# POWER_SWITCH.net
KiCad netlist of a schematic drawn in Altium Designer
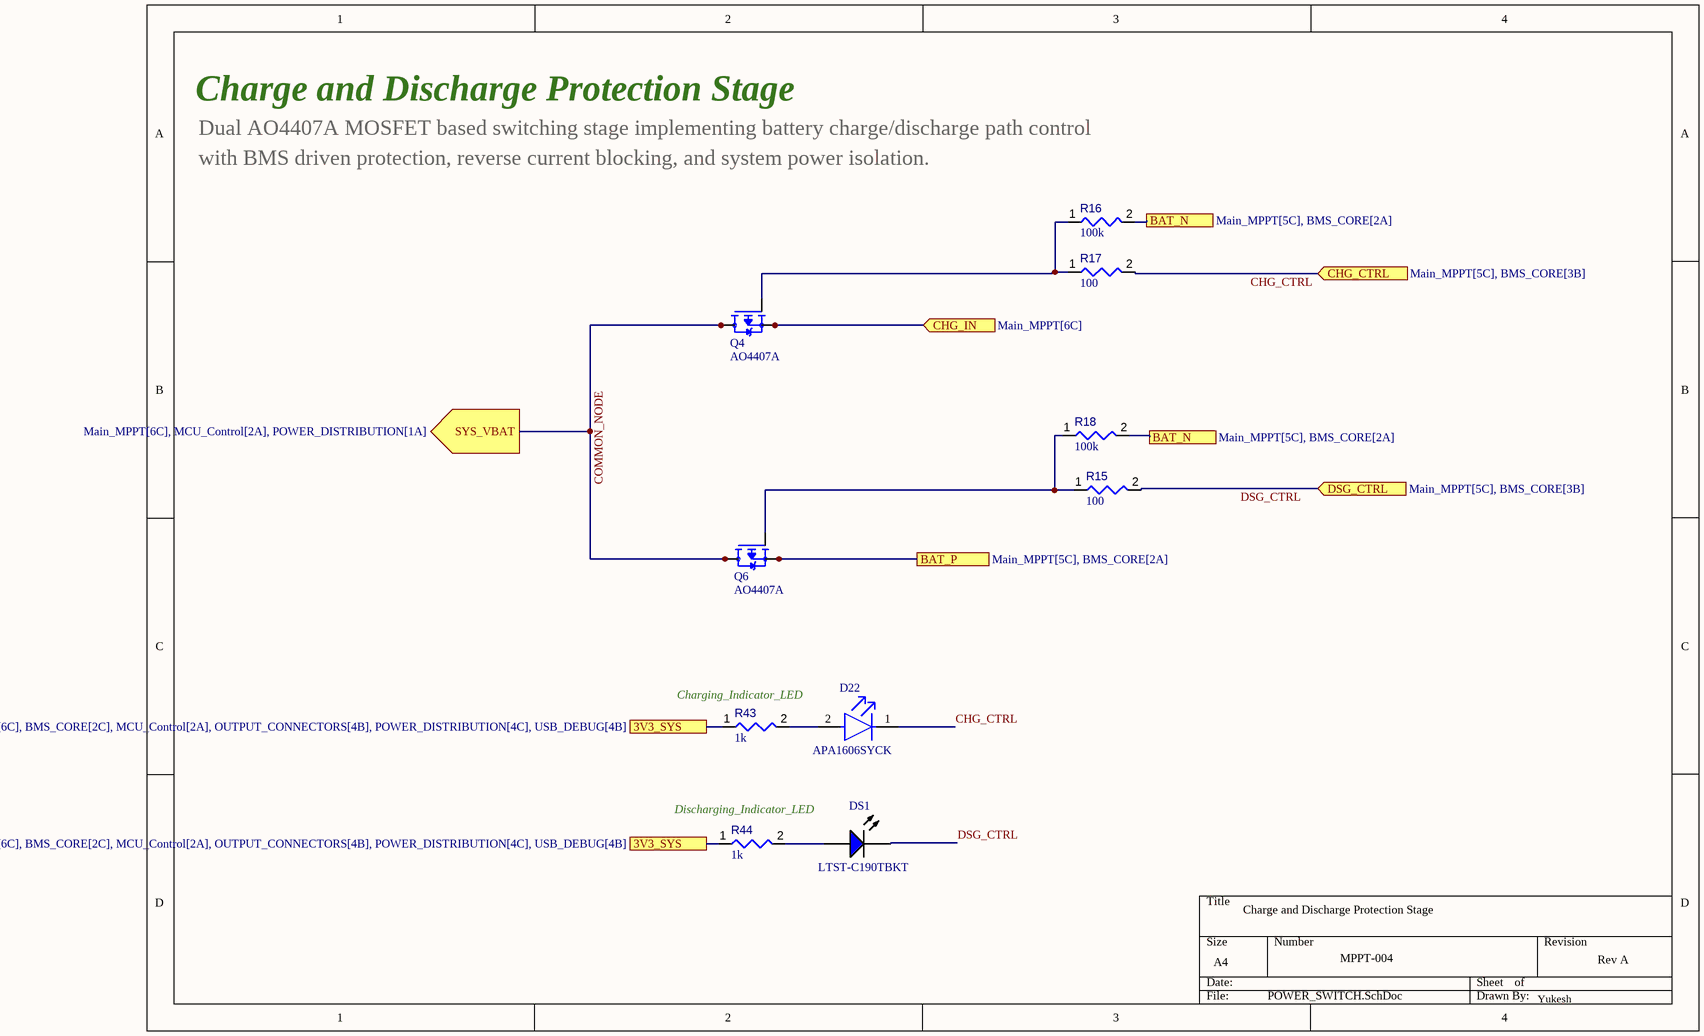
[diagram p0: POWER_SWITCH.SchDoc]

(export (version "E")
  (design (tool "Eeschema 10.0.6"))
  (components
    (comp (ref "D22")
      (value "APA1606SYCK")
      (footprint "FP-APA1606SYCK-MFG")
      (description "LED YELLOW CLEAR CHIP SMD R/A")
      (libsource (lib "Altium Content Vault") (part "8706943c75ba83719d021d2fdc84c58"))
    )
    (comp (ref "DS1")
      (value "LTST-C190TBKT")
      (footprint "LTST-C190TBKT-2_V")
      (description "Single Color Chip LED, 2.8 to 3.8 V, 28 to 180 mcd, -20 to 80 degC, 2-Pin SMD, RoHS, Tape and Reel")
      (libsource (lib "Altium Content Vault") (part "LED-BLUE-AK-2"))
    )
    (comp (ref "Q4")
      (value "AO4407A")
      (footprint "SOIC127P600X175-8N")
      (description "P-Channel 30 V 12A (Ta) 3.1W (Ta) Surface Mount 8-SOIC")
      (fields (field (name "MF") "Alpha &"))
      (libsource (lib "YUKESH S") (part "AO4407A"))
    )
    (comp (ref "Q6")
      (value "AO4407A")
      (footprint "SOIC127P600X175-8N")
      (description "P-Channel 30 V 12A (Ta) 3.1W (Ta) Surface Mount 8-SOIC")
      (fields (field (name "MF") "Alpha &"))
      (libsource (lib "YUKESH S") (part "AO4407A"))
    )
    (comp (ref "R15")
      (value "100")
      (footprint "RESC0402(1005)_L")
      (description "100R 0.063W 1% 0402 (1005 Metric)  SMD")
      (fields (field (name "TOLERANCE") "1%") (field (name "POWER") "63mW"))
      (libsource (lib "YUKESH S") (part "100R2F"))
    )
    (comp (ref "R16")
      (value "100k")
      (footprint "RESC0402(1005)_L")
      (description "100K 0.063W 1% 0402 (1005 Metric)  SMD")
      (fields (field (name "POWER") "63mW") (field (name "TOLERANCE") "1%"))
      (libsource (lib "YUKESH S") (part "100KR2F"))
    )
    (comp (ref "R17")
      (value "100")
      (footprint "RESC0402(1005)_L")
      (description "100R 0.063W 1% 0402 (1005 Metric)  SMD")
      (fields (field (name "TOLERANCE") "1%") (field (name "POWER") "63mW"))
      (libsource (lib "YUKESH S") (part "100R2F"))
    )
    (comp (ref "R18")
      (value "100k")
      (footprint "RESC0402(1005)_L")
      (description "100K 0.063W 1% 0402 (1005 Metric)  SMD")
      (fields (field (name "POWER") "63mW") (field (name "TOLERANCE") "1%"))
      (libsource (lib "YUKESH S") (part "100KR2F"))
    )
    (comp (ref "R43")
      (value "1k")
      (footprint "RESC0402(1005)_L")
      (description "1K 0.063W 5% 0402 (1005 Metric)  SMD")
      (fields (field (name "POWER") "63mW") (field (name "TOLERANCE") "5%"))
      (libsource (lib "YUKESH S") (part "1KR2J"))
    )
    (comp (ref "R44")
      (value "1k")
      (footprint "RESC0402(1005)_L")
      (description "1K 0.063W 5% 0402 (1005 Metric)  SMD")
      (fields (field (name "POWER") "63mW") (field (name "TOLERANCE") "5%"))
      (libsource (lib "YUKESH S") (part "1KR2J"))
    )
  )
  (nets
    (net (code "1") (name "/3V3_SYS") (class "Default")
      (node (ref "R43") (pin "1") (pinfunction "1_1") (pintype "passive"))
      (node (ref "R44") (pin "1") (pinfunction "1_1") (pintype "passive"))
    )
    (net (code "2") (name "/BAT_N") (class "Default")
      (node (ref "R16") (pin "2") (pinfunction "2_2") (pintype "passive"))
      (node (ref "R18") (pin "2") (pinfunction "2_2") (pintype "passive"))
    )
    (net (code "3") (name "/BAT_P") (class "Default")
      (node (ref "Q6") (pin "1") (pinfunction "S_1") (pintype "passive"))
      (node (ref "Q6") (pin "2") (pinfunction "S_2") (pintype "passive"))
      (node (ref "Q6") (pin "3") (pinfunction "S_3") (pintype "passive"))
    )
    (net (code "4") (name "/CHG_CTRL") (class "Default")
      (node (ref "D22") (pin "1") (pinfunction "C_1") (pintype "passive"))
      (node (ref "R17") (pin "2") (pinfunction "2_2") (pintype "passive"))
    )
    (net (code "5") (name "/CHG_IN") (class "Default")
      (node (ref "Q4") (pin "1") (pinfunction "S_1") (pintype "passive"))
      (node (ref "Q4") (pin "2") (pinfunction "S_2") (pintype "passive"))
      (node (ref "Q4") (pin "3") (pinfunction "S_3") (pintype "passive"))
    )
    (net (code "6") (name "/COMMON_NODE") (class "Default")
      (node (ref "Q4") (pin "5") (pinfunction "D_5") (pintype "passive"))
      (node (ref "Q4") (pin "6") (pinfunction "D_6") (pintype "passive"))
      (node (ref "Q4") (pin "7") (pinfunction "D_7") (pintype "passive"))
      (node (ref "Q4") (pin "8") (pinfunction "D_8") (pintype "passive"))
      (node (ref "Q6") (pin "5") (pinfunction "D_5") (pintype "passive"))
      (node (ref "Q6") (pin "6") (pinfunction "D_6") (pintype "passive"))
      (node (ref "Q6") (pin "7") (pinfunction "D_7") (pintype "passive"))
      (node (ref "Q6") (pin "8") (pinfunction "D_8") (pintype "passive"))
    )
    (net (code "7") (name "/DSG_CTRL") (class "Default")
      (node (ref "DS1") (pin "2") (pinfunction "K_2") (pintype "passive"))
      (node (ref "R15") (pin "2") (pinfunction "2_2") (pintype "passive"))
    )
    (net (code "8") (name "Net-(D22-A)") (class "Default")
      (node (ref "D22") (pin "2") (pinfunction "A_2") (pintype "passive"))
      (node (ref "R43") (pin "2") (pinfunction "2_2") (pintype "passive"))
    )
    (net (code "9") (name "Net-(DS1-A)") (class "Default")
      (node (ref "DS1") (pin "1") (pinfunction "A_1") (pintype "passive"))
      (node (ref "R44") (pin "2") (pinfunction "2_2") (pintype "passive"))
    )
    (net (code "10") (name "Net-(Q4-G)") (class "Default")
      (node (ref "Q4") (pin "4") (pinfunction "G_4") (pintype "passive"))
      (node (ref "R16") (pin "1") (pinfunction "1_1") (pintype "passive"))
      (node (ref "R17") (pin "1") (pinfunction "1_1") (pintype "passive"))
    )
    (net (code "11") (name "Net-(Q6-G)") (class "Default")
      (node (ref "Q6") (pin "4") (pinfunction "G_4") (pintype "passive"))
      (node (ref "R15") (pin "1") (pinfunction "1_1") (pintype "passive"))
      (node (ref "R18") (pin "1") (pinfunction "1_1") (pintype "passive"))
    )
  )
)
